# 20170814_DukeExperimentalHeadstageAmplif.net
KiCad netlist of a schematic drawn in EAGLE
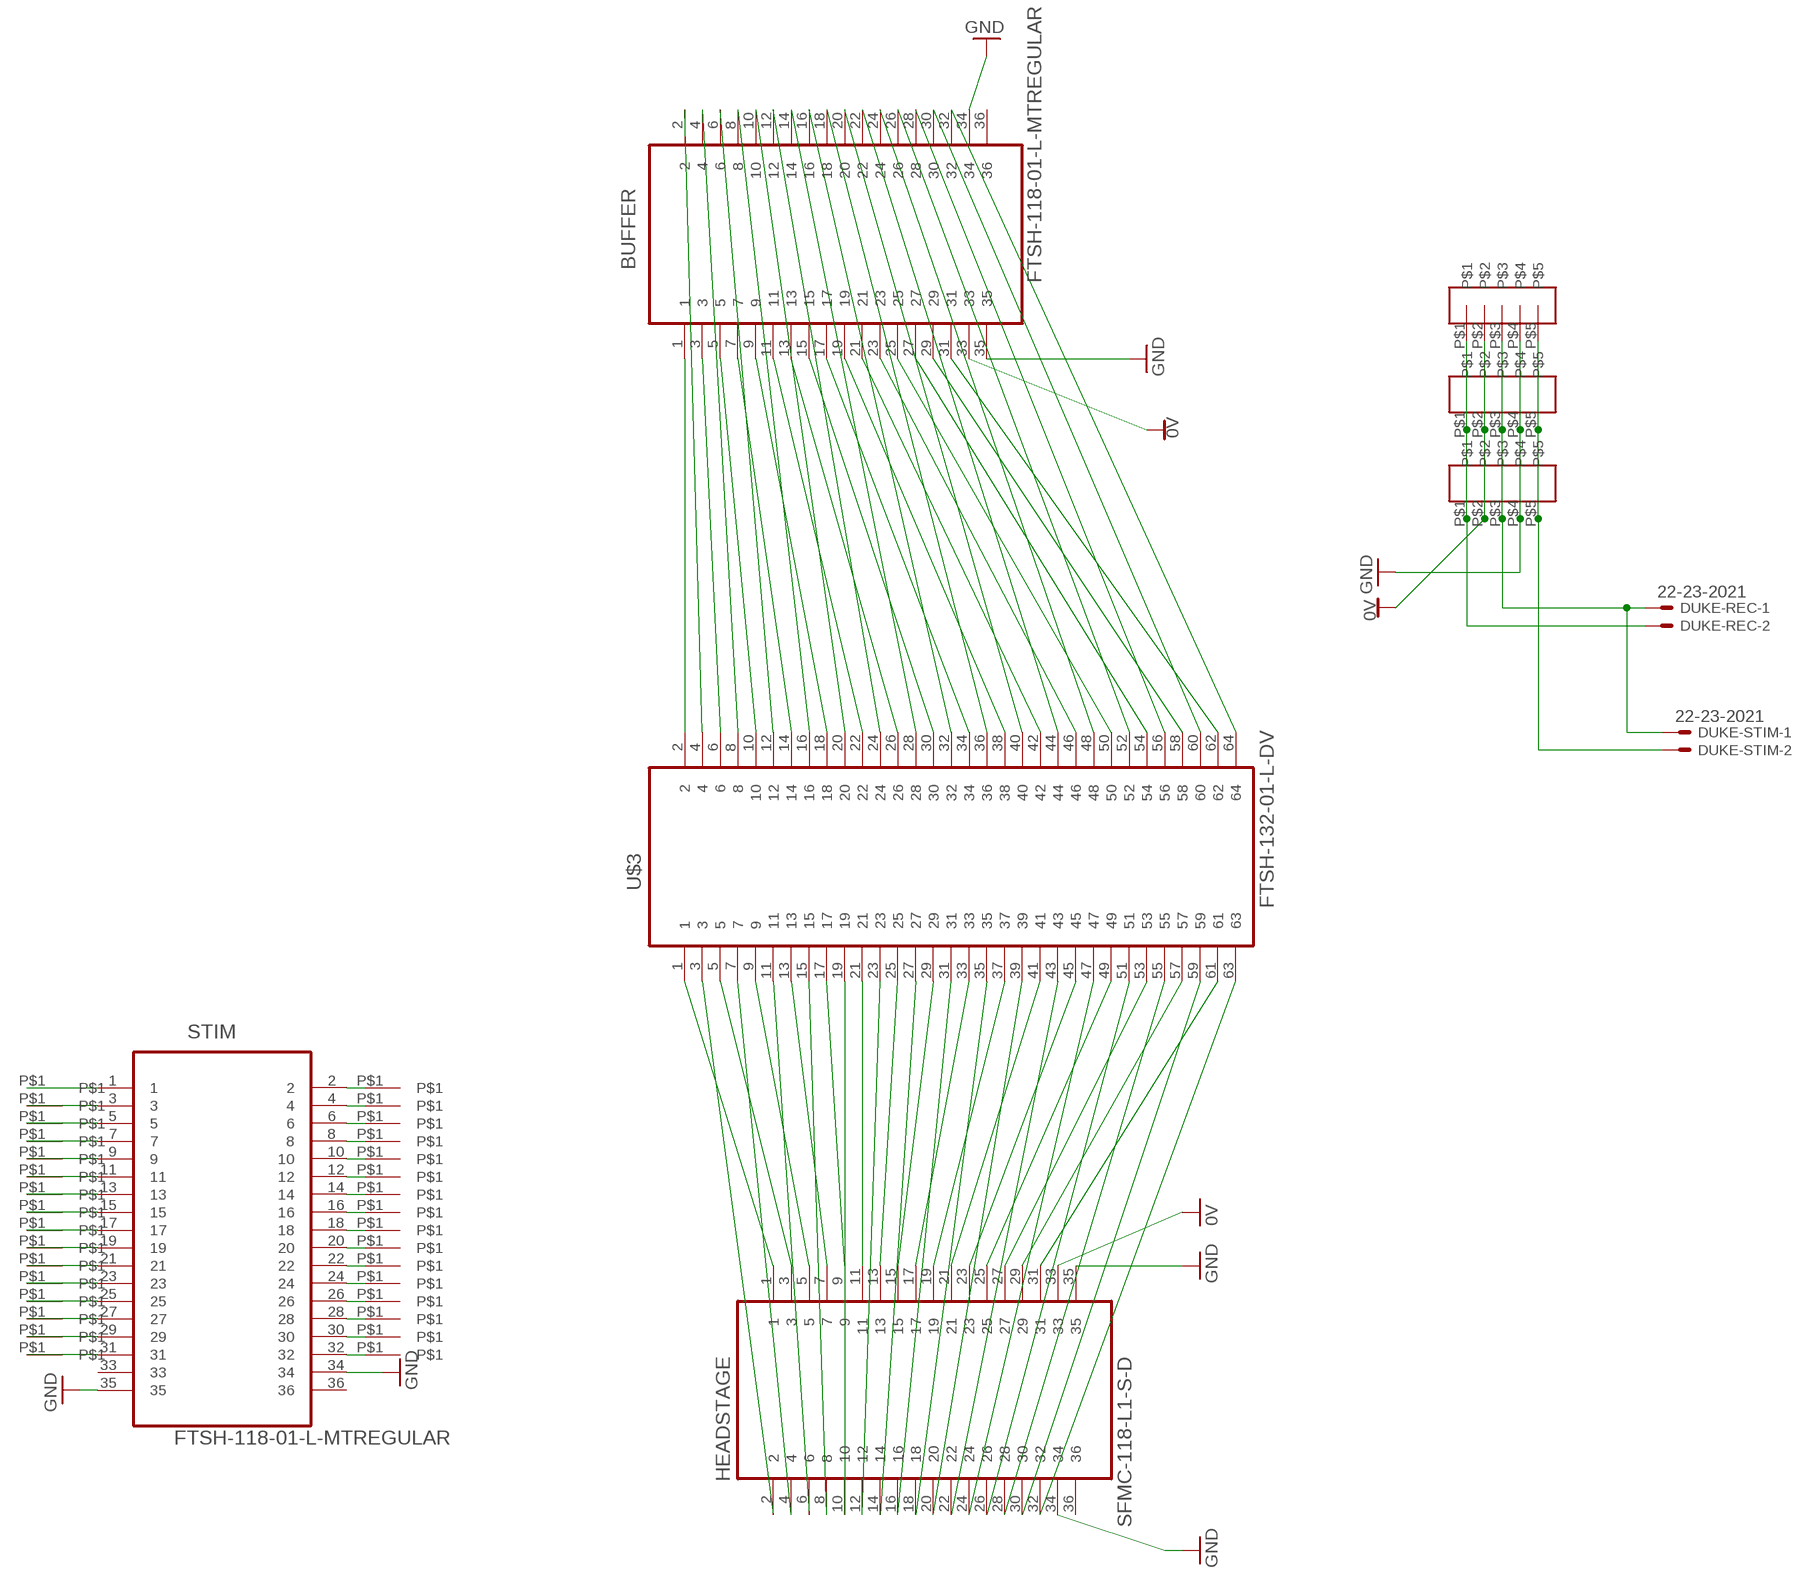
[diagram p0: schematic, sheet 1]

(export (version "E")
  (design (tool "Eeschema 10.0.6"))
  (components
    (comp (ref "BUFFER")
      (value "FTSH-118-01-L-MTREGULAR")
      (footprint "eagle-import:FTSH-118-01-L-MT")
      (libsource (lib "eagle-import") (part "FTSH-118-01-L-MTREGULAR"))
    )
    (comp (ref "DUKE-REC")
      (value "22-23-2021")
      (footprint "eagle-import:22-23-2021")
      (fields (field (name "MF") "MOLEX"))
      (libsource (lib "eagle-import") (part "22-23-2021"))
    )
    (comp (ref "DUKE-STIM")
      (value "22-23-2021")
      (footprint "eagle-import:22-23-2021")
      (fields (field (name "MF") "MOLEX"))
      (libsource (lib "eagle-import") (part "22-23-2021"))
    )
    (comp (ref "HEADSTAGE")
      (value "SFMC-118-L1-S-D")
      (footprint "eagle-import:SFMC-118-L1-S-D")
      (libsource (lib "eagle-import") (part "SFMC-118-L1-S-D"))
    )
    (comp (ref "STIM")
      (value "FTSH-118-01-L-MTREGULAR")
      (footprint "eagle-import:FTSH-118-01-L-MT")
      (libsource (lib "eagle-import") (part "FTSH-118-01-L-MTREGULAR"))
    )
    (comp (ref "U$1")
      (value "VIA")
      (footprint "eagle-import:VIA")
      (libsource (lib "eagle-import") (part "VIA"))
    )
    (comp (ref "U$2")
      (value "VIA")
      (footprint "eagle-import:VIA")
      (libsource (lib "eagle-import") (part "VIA"))
    )
    (comp (ref "U$3")
      (value "FTSH-132-01-L-DV")
      (footprint "eagle-import:FTSH-132-01-DV")
      (libsource (lib "eagle-import") (part "FTSH-132-01-L-DV"))
    )
    (comp (ref "U$4")
      (value "VIA")
      (footprint "eagle-import:VIA")
      (libsource (lib "eagle-import") (part "VIA"))
    )
    (comp (ref "U$5")
      (value "VIA")
      (footprint "eagle-import:VIA")
      (libsource (lib "eagle-import") (part "VIA"))
    )
    (comp (ref "U$6")
      (value "VIA")
      (footprint "eagle-import:VIA")
      (libsource (lib "eagle-import") (part "VIA"))
    )
    (comp (ref "U$7")
      (value "VIA")
      (footprint "eagle-import:VIA")
      (libsource (lib "eagle-import") (part "VIA"))
    )
    (comp (ref "U$8")
      (value "VIA")
      (footprint "eagle-import:VIA")
      (libsource (lib "eagle-import") (part "VIA"))
    )
    (comp (ref "U$9")
      (value "VIA")
      (footprint "eagle-import:VIA")
      (libsource (lib "eagle-import") (part "VIA"))
    )
    (comp (ref "U$10")
      (value "VIA")
      (footprint "eagle-import:VIA")
      (libsource (lib "eagle-import") (part "VIA"))
    )
    (comp (ref "U$11")
      (value "VIA")
      (footprint "eagle-import:VIA")
      (libsource (lib "eagle-import") (part "VIA"))
    )
    (comp (ref "U$12")
      (value "VIA")
      (footprint "eagle-import:VIA")
      (libsource (lib "eagle-import") (part "VIA"))
    )
    (comp (ref "U$13")
      (value "VIA")
      (footprint "eagle-import:VIA")
      (libsource (lib "eagle-import") (part "VIA"))
    )
    (comp (ref "U$14")
      (value "VIA")
      (footprint "eagle-import:VIA")
      (libsource (lib "eagle-import") (part "VIA"))
    )
    (comp (ref "U$15")
      (value "VIA")
      (footprint "eagle-import:VIA")
      (libsource (lib "eagle-import") (part "VIA"))
    )
    (comp (ref "U$16")
      (value "VIA")
      (footprint "eagle-import:VIA")
      (libsource (lib "eagle-import") (part "VIA"))
    )
    (comp (ref "U$17")
      (value "VIA")
      (footprint "eagle-import:VIA")
      (libsource (lib "eagle-import") (part "VIA"))
    )
    (comp (ref "U$18")
      (value "VIA")
      (footprint "eagle-import:VIA")
      (libsource (lib "eagle-import") (part "VIA"))
    )
    (comp (ref "U$19")
      (value "VIA")
      (footprint "eagle-import:VIA")
      (libsource (lib "eagle-import") (part "VIA"))
    )
    (comp (ref "U$20")
      (value "VIA")
      (footprint "eagle-import:VIA")
      (libsource (lib "eagle-import") (part "VIA"))
    )
    (comp (ref "U$21")
      (value "VIA")
      (footprint "eagle-import:VIA")
      (libsource (lib "eagle-import") (part "VIA"))
    )
    (comp (ref "U$22")
      (value "VIA")
      (footprint "eagle-import:VIA")
      (libsource (lib "eagle-import") (part "VIA"))
    )
    (comp (ref "U$23")
      (value "VIA")
      (footprint "eagle-import:VIA")
      (libsource (lib "eagle-import") (part "VIA"))
    )
    (comp (ref "U$24")
      (value "VIA")
      (footprint "eagle-import:VIA")
      (libsource (lib "eagle-import") (part "VIA"))
    )
    (comp (ref "U$25")
      (value "VIA")
      (footprint "eagle-import:VIA")
      (libsource (lib "eagle-import") (part "VIA"))
    )
    (comp (ref "U$26")
      (value "VIA")
      (footprint "eagle-import:VIA")
      (libsource (lib "eagle-import") (part "VIA"))
    )
    (comp (ref "U$27")
      (value "VIA")
      (footprint "eagle-import:VIA")
      (libsource (lib "eagle-import") (part "VIA"))
    )
    (comp (ref "U$28")
      (value "VIA")
      (footprint "eagle-import:VIA")
      (libsource (lib "eagle-import") (part "VIA"))
    )
    (comp (ref "U$29")
      (value "VIA")
      (footprint "eagle-import:VIA")
      (libsource (lib "eagle-import") (part "VIA"))
    )
    (comp (ref "U$30")
      (value "VIA")
      (footprint "eagle-import:VIA")
      (libsource (lib "eagle-import") (part "VIA"))
    )
    (comp (ref "U$31")
      (value "VIA")
      (footprint "eagle-import:VIA")
      (libsource (lib "eagle-import") (part "VIA"))
    )
    (comp (ref "U$32")
      (value "VIA")
      (footprint "eagle-import:VIA")
      (libsource (lib "eagle-import") (part "VIA"))
    )
    (comp (ref "U$33")
      (value "VIA")
      (footprint "eagle-import:VIA")
      (libsource (lib "eagle-import") (part "VIA"))
    )
    (comp (ref "U$34")
      (value "LPPB051NFFN-RC")
      (footprint "eagle-import:LPPB051NFFN-RC")
      (libsource (lib "eagle-import") (part "LPPB051NFFN-RC"))
    )
    (comp (ref "U$35")
      (value "LPPB051NFFN-RC")
      (footprint "eagle-import:LPPB051NFFN-RC")
      (libsource (lib "eagle-import") (part "LPPB051NFFN-RC"))
    )
    (comp (ref "U$36")
      (value "LPPB051NFFN-RC")
      (footprint "eagle-import:LPPB051NFFN-RC")
      (libsource (lib "eagle-import") (part "LPPB051NFFN-RC"))
    )
  )
  (nets
    (net (code "1") (name "0V") (class "Default")
      (node (ref "BUFFER") (pin "33") (pinfunction "33_33") (pintype "passive"))
      (node (ref "HEADSTAGE") (pin "33") (pinfunction "33_33") (pintype "passive"))
      (node (ref "U$34") (pin "P$2") (pinfunction "P$2_P$2") (pintype "bidirectional"))
      (node (ref "U$35") (pin "P$2") (pinfunction "P$2_P$2") (pintype "bidirectional"))
      (node (ref "U$36") (pin "P$2") (pinfunction "P$2_P$2") (pintype "bidirectional"))
    )
    (net (code "2") (name "GND") (class "Default")
      (node (ref "BUFFER") (pin "34") (pinfunction "34_34") (pintype "passive"))
      (node (ref "BUFFER") (pin "35") (pinfunction "35_35") (pintype "passive"))
      (node (ref "HEADSTAGE") (pin "34") (pinfunction "34_34") (pintype "passive"))
      (node (ref "HEADSTAGE") (pin "35") (pinfunction "35_35") (pintype "passive"))
      (node (ref "STIM") (pin "34") (pinfunction "34_34") (pintype "passive"))
      (node (ref "STIM") (pin "35") (pinfunction "35_35") (pintype "passive"))
      (node (ref "U$34") (pin "P$4") (pinfunction "P$4_P$4") (pintype "bidirectional"))
      (node (ref "U$35") (pin "P$4") (pinfunction "P$4_P$4") (pintype "bidirectional"))
      (node (ref "U$36") (pin "P$4") (pinfunction "P$4_P$4") (pintype "bidirectional"))
    )
    (net (code "3") (name "Net-(BUFFER-Pad1)") (class "Default")
      (node (ref "BUFFER") (pin "1") (pinfunction "1_1") (pintype "passive"))
      (node (ref "U$3") (pin "2") (pinfunction "2_2") (pintype "passive"))
    )
    (net (code "4") (name "Net-(BUFFER-Pad2)") (class "Default")
      (node (ref "BUFFER") (pin "2") (pinfunction "2_2") (pintype "passive"))
      (node (ref "U$3") (pin "4") (pinfunction "4_4") (pintype "passive"))
    )
    (net (code "5") (name "Net-(BUFFER-Pad3)") (class "Default")
      (node (ref "BUFFER") (pin "3") (pinfunction "3_3") (pintype "passive"))
      (node (ref "U$3") (pin "6") (pinfunction "6_6") (pintype "passive"))
    )
    (net (code "6") (name "Net-(BUFFER-Pad4)") (class "Default")
      (node (ref "BUFFER") (pin "4") (pinfunction "4_4") (pintype "passive"))
      (node (ref "U$3") (pin "8") (pinfunction "8_8") (pintype "passive"))
    )
    (net (code "7") (name "Net-(BUFFER-Pad5)") (class "Default")
      (node (ref "BUFFER") (pin "5") (pinfunction "5_5") (pintype "passive"))
      (node (ref "U$3") (pin "10") (pinfunction "10_10") (pintype "passive"))
    )
    (net (code "8") (name "Net-(BUFFER-Pad6)") (class "Default")
      (node (ref "BUFFER") (pin "6") (pinfunction "6_6") (pintype "passive"))
      (node (ref "U$3") (pin "12") (pinfunction "12_12") (pintype "passive"))
    )
    (net (code "9") (name "Net-(BUFFER-Pad7)") (class "Default")
      (node (ref "BUFFER") (pin "7") (pinfunction "7_7") (pintype "passive"))
      (node (ref "U$3") (pin "14") (pinfunction "14_14") (pintype "passive"))
    )
    (net (code "10") (name "Net-(BUFFER-Pad8)") (class "Default")
      (node (ref "BUFFER") (pin "8") (pinfunction "8_8") (pintype "passive"))
      (node (ref "U$3") (pin "16") (pinfunction "16_16") (pintype "passive"))
    )
    (net (code "11") (name "Net-(BUFFER-Pad9)") (class "Default")
      (node (ref "BUFFER") (pin "9") (pinfunction "9_9") (pintype "passive"))
      (node (ref "U$3") (pin "18") (pinfunction "18_18") (pintype "passive"))
    )
    (net (code "12") (name "Net-(BUFFER-Pad10)") (class "Default")
      (node (ref "BUFFER") (pin "10") (pinfunction "10_10") (pintype "passive"))
      (node (ref "U$3") (pin "20") (pinfunction "20_20") (pintype "passive"))
    )
    (net (code "13") (name "Net-(BUFFER-Pad11)") (class "Default")
      (node (ref "BUFFER") (pin "11") (pinfunction "11_11") (pintype "passive"))
      (node (ref "U$3") (pin "22") (pinfunction "22_22") (pintype "passive"))
    )
    (net (code "14") (name "Net-(BUFFER-Pad12)") (class "Default")
      (node (ref "BUFFER") (pin "12") (pinfunction "12_12") (pintype "passive"))
      (node (ref "U$3") (pin "24") (pinfunction "24_24") (pintype "passive"))
    )
    (net (code "15") (name "Net-(BUFFER-Pad13)") (class "Default")
      (node (ref "BUFFER") (pin "13") (pinfunction "13_13") (pintype "passive"))
      (node (ref "U$3") (pin "26") (pinfunction "26_26") (pintype "passive"))
    )
    (net (code "16") (name "Net-(BUFFER-Pad14)") (class "Default")
      (node (ref "BUFFER") (pin "14") (pinfunction "14_14") (pintype "passive"))
      (node (ref "U$3") (pin "28") (pinfunction "28_28") (pintype "passive"))
    )
    (net (code "17") (name "Net-(BUFFER-Pad15)") (class "Default")
      (node (ref "BUFFER") (pin "15") (pinfunction "15_15") (pintype "passive"))
      (node (ref "U$3") (pin "30") (pinfunction "30_30") (pintype "passive"))
    )
    (net (code "18") (name "Net-(BUFFER-Pad16)") (class "Default")
      (node (ref "BUFFER") (pin "16") (pinfunction "16_16") (pintype "passive"))
      (node (ref "U$3") (pin "32") (pinfunction "32_32") (pintype "passive"))
    )
    (net (code "19") (name "Net-(BUFFER-Pad17)") (class "Default")
      (node (ref "BUFFER") (pin "17") (pinfunction "17_17") (pintype "passive"))
      (node (ref "U$3") (pin "34") (pinfunction "34_34") (pintype "passive"))
    )
    (net (code "20") (name "Net-(BUFFER-Pad18)") (class "Default")
      (node (ref "BUFFER") (pin "18") (pinfunction "18_18") (pintype "passive"))
      (node (ref "U$3") (pin "36") (pinfunction "36_36") (pintype "passive"))
    )
    (net (code "21") (name "Net-(BUFFER-Pad19)") (class "Default")
      (node (ref "BUFFER") (pin "19") (pinfunction "19_19") (pintype "passive"))
      (node (ref "U$3") (pin "38") (pinfunction "38_38") (pintype "bidirectional"))
    )
    (net (code "22") (name "Net-(BUFFER-Pad20)") (class "Default")
      (node (ref "BUFFER") (pin "20") (pinfunction "20_20") (pintype "passive"))
      (node (ref "U$3") (pin "40") (pinfunction "40_40") (pintype "bidirectional"))
    )
    (net (code "23") (name "Net-(BUFFER-Pad21)") (class "Default")
      (node (ref "BUFFER") (pin "21") (pinfunction "21_21") (pintype "passive"))
      (node (ref "U$3") (pin "42") (pinfunction "42_42") (pintype "bidirectional"))
    )
    (net (code "24") (name "Net-(BUFFER-Pad22)") (class "Default")
      (node (ref "BUFFER") (pin "22") (pinfunction "22_22") (pintype "passive"))
      (node (ref "U$3") (pin "44") (pinfunction "44_44") (pintype "bidirectional"))
    )
    (net (code "25") (name "Net-(BUFFER-Pad23)") (class "Default")
      (node (ref "BUFFER") (pin "23") (pinfunction "23_23") (pintype "passive"))
      (node (ref "U$3") (pin "46") (pinfunction "46_46") (pintype "bidirectional"))
    )
    (net (code "26") (name "Net-(BUFFER-Pad24)") (class "Default")
      (node (ref "BUFFER") (pin "24") (pinfunction "24_24") (pintype "passive"))
      (node (ref "U$3") (pin "48") (pinfunction "48_48") (pintype "bidirectional"))
    )
    (net (code "27") (name "Net-(BUFFER-Pad25)") (class "Default")
      (node (ref "BUFFER") (pin "25") (pinfunction "25_25") (pintype "passive"))
      (node (ref "U$3") (pin "50") (pinfunction "50_50") (pintype "bidirectional"))
    )
    (net (code "28") (name "Net-(BUFFER-Pad26)") (class "Default")
      (node (ref "BUFFER") (pin "26") (pinfunction "26_26") (pintype "passive"))
      (node (ref "U$3") (pin "52") (pinfunction "52_52") (pintype "bidirectional"))
    )
    (net (code "29") (name "Net-(BUFFER-Pad27)") (class "Default")
      (node (ref "BUFFER") (pin "27") (pinfunction "27_27") (pintype "passive"))
      (node (ref "U$3") (pin "54") (pinfunction "54_54") (pintype "bidirectional"))
    )
    (net (code "30") (name "Net-(BUFFER-Pad28)") (class "Default")
      (node (ref "BUFFER") (pin "28") (pinfunction "28_28") (pintype "passive"))
      (node (ref "U$3") (pin "56") (pinfunction "56_56") (pintype "bidirectional"))
    )
    (net (code "31") (name "Net-(BUFFER-Pad29)") (class "Default")
      (node (ref "BUFFER") (pin "29") (pinfunction "29_29") (pintype "passive"))
      (node (ref "U$3") (pin "58") (pinfunction "58_58") (pintype "bidirectional"))
    )
    (net (code "32") (name "Net-(BUFFER-Pad30)") (class "Default")
      (node (ref "BUFFER") (pin "30") (pinfunction "30_30") (pintype "passive"))
      (node (ref "U$3") (pin "60") (pinfunction "60_60") (pintype "bidirectional"))
    )
    (net (code "33") (name "Net-(BUFFER-Pad31)") (class "Default")
      (node (ref "BUFFER") (pin "31") (pinfunction "31_31") (pintype "passive"))
      (node (ref "U$3") (pin "62") (pinfunction "62_62") (pintype "bidirectional"))
    )
    (net (code "34") (name "Net-(BUFFER-Pad32)") (class "Default")
      (node (ref "BUFFER") (pin "32") (pinfunction "32_32") (pintype "passive"))
      (node (ref "U$3") (pin "64") (pinfunction "64_64") (pintype "bidirectional"))
    )
    (net (code "35") (name "Net-(DUKE-RECA-S)") (class "Default")
      (node (ref "DUKE-REC") (pin "1") (pinfunction "S_1") (pintype "passive"))
      (node (ref "DUKE-STIM") (pin "1") (pinfunction "S_1") (pintype "passive"))
      (node (ref "U$34") (pin "P$3") (pinfunction "P$3_P$3") (pintype "bidirectional"))
      (node (ref "U$35") (pin "P$3") (pinfunction "P$3_P$3") (pintype "bidirectional"))
      (node (ref "U$36") (pin "P$3") (pinfunction "P$3_P$3") (pintype "bidirectional"))
    )
    (net (code "36") (name "Net-(DUKE-RECB-S)") (class "Default")
      (node (ref "DUKE-REC") (pin "2") (pinfunction "S_2") (pintype "passive"))
      (node (ref "U$34") (pin "P$1") (pinfunction "P$1_P$1") (pintype "bidirectional"))
      (node (ref "U$35") (pin "P$1") (pinfunction "P$1_P$1") (pintype "bidirectional"))
      (node (ref "U$36") (pin "P$1") (pinfunction "P$1_P$1") (pintype "bidirectional"))
    )
    (net (code "37") (name "Net-(DUKE-STIMB-S)") (class "Default")
      (node (ref "DUKE-STIM") (pin "2") (pinfunction "S_2") (pintype "passive"))
      (node (ref "U$34") (pin "P$5") (pinfunction "P$5_P$5") (pintype "bidirectional"))
      (node (ref "U$35") (pin "P$5") (pinfunction "P$5_P$5") (pintype "bidirectional"))
      (node (ref "U$36") (pin "P$5") (pinfunction "P$5_P$5") (pintype "bidirectional"))
    )
    (net (code "38") (name "Net-(HEADSTAGE-Pad1)") (class "Default")
      (node (ref "HEADSTAGE") (pin "1") (pinfunction "1_1") (pintype "passive"))
      (node (ref "U$3") (pin "1") (pinfunction "1_1") (pintype "passive"))
    )
    (net (code "39") (name "Net-(HEADSTAGE-Pad2)") (class "Default")
      (node (ref "HEADSTAGE") (pin "2") (pinfunction "2_2") (pintype "passive"))
      (node (ref "U$3") (pin "3") (pinfunction "3_3") (pintype "passive"))
    )
    (net (code "40") (name "Net-(HEADSTAGE-Pad3)") (class "Default")
      (node (ref "HEADSTAGE") (pin "3") (pinfunction "3_3") (pintype "passive"))
      (node (ref "U$3") (pin "5") (pinfunction "5_5") (pintype "passive"))
    )
    (net (code "41") (name "Net-(HEADSTAGE-Pad4)") (class "Default")
      (node (ref "HEADSTAGE") (pin "4") (pinfunction "4_4") (pintype "passive"))
      (node (ref "U$3") (pin "7") (pinfunction "7_7") (pintype "passive"))
    )
    (net (code "42") (name "Net-(HEADSTAGE-Pad5)") (class "Default")
      (node (ref "HEADSTAGE") (pin "5") (pinfunction "5_5") (pintype "passive"))
      (node (ref "U$3") (pin "9") (pinfunction "9_9") (pintype "passive"))
    )
    (net (code "43") (name "Net-(HEADSTAGE-Pad6)") (class "Default")
      (node (ref "HEADSTAGE") (pin "6") (pinfunction "6_6") (pintype "passive"))
      (node (ref "U$3") (pin "11") (pinfunction "11_11") (pintype "passive"))
    )
    (net (code "44") (name "Net-(HEADSTAGE-Pad7)") (class "Default")
      (node (ref "HEADSTAGE") (pin "7") (pinfunction "7_7") (pintype "passive"))
      (node (ref "U$3") (pin "13") (pinfunction "13_13") (pintype "passive"))
    )
    (net (code "45") (name "Net-(HEADSTAGE-Pad8)") (class "Default")
      (node (ref "HEADSTAGE") (pin "8") (pinfunction "8_8") (pintype "passive"))
      (node (ref "U$3") (pin "15") (pinfunction "15_15") (pintype "passive"))
    )
    (net (code "46") (name "Net-(HEADSTAGE-Pad9)") (class "Default")
      (node (ref "HEADSTAGE") (pin "9") (pinfunction "9_9") (pintype "passive"))
      (node (ref "U$3") (pin "17") (pinfunction "17_17") (pintype "passive"))
    )
    (net (code "47") (name "Net-(HEADSTAGE-Pad10)") (class "Default")
      (node (ref "HEADSTAGE") (pin "10") (pinfunction "10_10") (pintype "passive"))
      (node (ref "U$3") (pin "19") (pinfunction "19_19") (pintype "passive"))
    )
    (net (code "48") (name "Net-(HEADSTAGE-Pad11)") (class "Default")
      (node (ref "HEADSTAGE") (pin "11") (pinfunction "11_11") (pintype "passive"))
      (node (ref "U$3") (pin "21") (pinfunction "21_21") (pintype "passive"))
    )
    (net (code "49") (name "Net-(HEADSTAGE-Pad12)") (class "Default")
      (node (ref "HEADSTAGE") (pin "12") (pinfunction "12_12") (pintype "passive"))
      (node (ref "U$3") (pin "23") (pinfunction "23_23") (pintype "passive"))
    )
    (net (code "50") (name "Net-(HEADSTAGE-Pad13)") (class "Default")
      (node (ref "HEADSTAGE") (pin "13") (pinfunction "13_13") (pintype "passive"))
      (node (ref "U$3") (pin "25") (pinfunction "25_25") (pintype "passive"))
    )
    (net (code "51") (name "Net-(HEADSTAGE-Pad14)") (class "Default")
      (node (ref "HEADSTAGE") (pin "14") (pinfunction "14_14") (pintype "passive"))
      (node (ref "U$3") (pin "27") (pinfunction "27_27") (pintype "passive"))
    )
    (net (code "52") (name "Net-(HEADSTAGE-Pad15)") (class "Default")
      (node (ref "HEADSTAGE") (pin "15") (pinfunction "15_15") (pintype "passive"))
      (node (ref "U$3") (pin "29") (pinfunction "29_29") (pintype "passive"))
    )
    (net (code "53") (name "Net-(HEADSTAGE-Pad16)") (class "Default")
      (node (ref "HEADSTAGE") (pin "16") (pinfunction "16_16") (pintype "passive"))
      (node (ref "U$3") (pin "31") (pinfunction "31_31") (pintype "passive"))
    )
    (net (code "54") (name "Net-(HEADSTAGE-Pad17)") (class "Default")
      (node (ref "HEADSTAGE") (pin "17") (pinfunction "17_17") (pintype "passive"))
      (node (ref "U$3") (pin "33") (pinfunction "33_33") (pintype "passive"))
    )
    (net (code "55") (name "Net-(HEADSTAGE-Pad18)") (class "Default")
      (node (ref "HEADSTAGE") (pin "18") (pinfunction "18_18") (pintype "passive"))
      (node (ref "U$3") (pin "35") (pinfunction "35_35") (pintype "passive"))
    )
    (net (code "56") (name "Net-(HEADSTAGE-Pad19)") (class "Default")
      (node (ref "HEADSTAGE") (pin "19") (pinfunction "19_19") (pintype "passive"))
      (node (ref "U$3") (pin "37") (pinfunction "37_37") (pintype "bidirectional"))
    )
    (net (code "57") (name "Net-(HEADSTAGE-Pad20)") (class "Default")
      (node (ref "HEADSTAGE") (pin "20") (pinfunction "20_20") (pintype "passive"))
      (node (ref "U$3") (pin "39") (pinfunction "39_39") (pintype "bidirectional"))
    )
    (net (code "58") (name "Net-(HEADSTAGE-Pad21)") (class "Default")
      (node (ref "HEADSTAGE") (pin "21") (pinfunction "21_21") (pintype "passive"))
      (node (ref "U$3") (pin "41") (pinfunction "41_41") (pintype "bidirectional"))
    )
    (net (code "59") (name "Net-(HEADSTAGE-Pad22)") (class "Default")
      (node (ref "HEADSTAGE") (pin "22") (pinfunction "22_22") (pintype "passive"))
      (node (ref "U$3") (pin "43") (pinfunction "43_43") (pintype "bidirectional"))
    )
    (net (code "60") (name "Net-(HEADSTAGE-Pad23)") (class "Default")
      (node (ref "HEADSTAGE") (pin "23") (pinfunction "23_23") (pintype "passive"))
      (node (ref "U$3") (pin "45") (pinfunction "45_45") (pintype "bidirectional"))
    )
    (net (code "61") (name "Net-(HEADSTAGE-Pad24)") (class "Default")
      (node (ref "HEADSTAGE") (pin "24") (pinfunction "24_24") (pintype "passive"))
      (node (ref "U$3") (pin "47") (pinfunction "47_47") (pintype "bidirectional"))
    )
    (net (code "62") (name "Net-(HEADSTAGE-Pad25)") (class "Default")
      (node (ref "HEADSTAGE") (pin "25") (pinfunction "25_25") (pintype "passive"))
      (node (ref "U$3") (pin "49") (pinfunction "49_49") (pintype "bidirectional"))
    )
    (net (code "63") (name "Net-(HEADSTAGE-Pad26)") (class "Default")
      (node (ref "HEADSTAGE") (pin "26") (pinfunction "26_26") (pintype "passive"))
      (node (ref "U$3") (pin "51") (pinfunction "51_51") (pintype "bidirectional"))
    )
    (net (code "64") (name "Net-(HEADSTAGE-Pad27)") (class "Default")
      (node (ref "HEADSTAGE") (pin "27") (pinfunction "27_27") (pintype "passive"))
      (node (ref "U$3") (pin "53") (pinfunction "53_53") (pintype "bidirectional"))
    )
    (net (code "65") (name "Net-(HEADSTAGE-Pad28)") (class "Default")
      (node (ref "HEADSTAGE") (pin "28") (pinfunction "28_28") (pintype "passive"))
      (node (ref "U$3") (pin "55") (pinfunction "55_55") (pintype "bidirectional"))
    )
    (net (code "66") (name "Net-(HEADSTAGE-Pad29)") (class "Default")
      (node (ref "HEADSTAGE") (pin "29") (pinfunction "29_29") (pintype "passive"))
      (node (ref "U$3") (pin "57") (pinfunction "57_57") (pintype "bidirectional"))
    )
    (net (code "67") (name "Net-(HEADSTAGE-Pad30)") (class "Default")
      (node (ref "HEADSTAGE") (pin "30") (pinfunction "30_30") (pintype "passive"))
      (node (ref "U$3") (pin "59") (pinfunction "59_59") (pintype "bidirectional"))
    )
    (net (code "68") (name "Net-(HEADSTAGE-Pad31)") (class "Default")
      (node (ref "HEADSTAGE") (pin "31") (pinfunction "31_31") (pintype "passive"))
      (node (ref "U$3") (pin "61") (pinfunction "61_61") (pintype "bidirectional"))
    )
    (net (code "69") (name "Net-(HEADSTAGE-Pad32)") (class "Default")
      (node (ref "HEADSTAGE") (pin "32") (pinfunction "32_32") (pintype "passive"))
      (node (ref "U$3") (pin "63") (pinfunction "63_63") (pintype "bidirectional"))
    )
    (net (code "70") (name "Net-(STIM-Pad1)") (class "Default")
      (node (ref "STIM") (pin "1") (pinfunction "1_1") (pintype "passive"))
      (node (ref "U$33") (pin "P$1") (pinfunction "P$1_P$1") (pintype "bidirectional"))
    )
    (net (code "71") (name "Net-(STIM-Pad2)") (class "Default")
      (node (ref "STIM") (pin "2") (pinfunction "2_2") (pintype "passive"))
      (node (ref "U$1") (pin "P$1") (pinfunction "P$1_P$1") (pintype "bidirectional"))
    )
    (net (code "72") (name "Net-(STIM-Pad3)") (class "Default")
      (node (ref "STIM") (pin "3") (pinfunction "3_3") (pintype "passive"))
      (node (ref "U$32") (pin "P$1") (pinfunction "P$1_P$1") (pintype "bidirectional"))
    )
    (net (code "73") (name "Net-(STIM-Pad4)") (class "Default")
      (node (ref "STIM") (pin "4") (pinfunction "4_4") (pintype "passive"))
      (node (ref "U$2") (pin "P$1") (pinfunction "P$1_P$1") (pintype "bidirectional"))
    )
    (net (code "74") (name "Net-(STIM-Pad5)") (class "Default")
      (node (ref "STIM") (pin "5") (pinfunction "5_5") (pintype "passive"))
      (node (ref "U$31") (pin "P$1") (pinfunction "P$1_P$1") (pintype "bidirectional"))
    )
    (net (code "75") (name "Net-(STIM-Pad6)") (class "Default")
      (node (ref "STIM") (pin "6") (pinfunction "6_6") (pintype "passive"))
      (node (ref "U$4") (pin "P$1") (pinfunction "P$1_P$1") (pintype "bidirectional"))
    )
    (net (code "76") (name "Net-(STIM-Pad7)") (class "Default")
      (node (ref "STIM") (pin "7") (pinfunction "7_7") (pintype "passive"))
      (node (ref "U$30") (pin "P$1") (pinfunction "P$1_P$1") (pintype "bidirectional"))
    )
    (net (code "77") (name "Net-(STIM-Pad8)") (class "Default")
      (node (ref "STIM") (pin "8") (pinfunction "8_8") (pintype "passive"))
      (node (ref "U$5") (pin "P$1") (pinfunction "P$1_P$1") (pintype "bidirectional"))
    )
    (net (code "78") (name "Net-(STIM-Pad9)") (class "Default")
      (node (ref "STIM") (pin "9") (pinfunction "9_9") (pintype "passive"))
      (node (ref "U$29") (pin "P$1") (pinfunction "P$1_P$1") (pintype "bidirectional"))
    )
    (net (code "79") (name "Net-(STIM-Pad10)") (class "Default")
      (node (ref "STIM") (pin "10") (pinfunction "10_10") (pintype "passive"))
      (node (ref "U$6") (pin "P$1") (pinfunction "P$1_P$1") (pintype "bidirectional"))
    )
    (net (code "80") (name "Net-(STIM-Pad11)") (class "Default")
      (node (ref "STIM") (pin "11") (pinfunction "11_11") (pintype "passive"))
      (node (ref "U$28") (pin "P$1") (pinfunction "P$1_P$1") (pintype "bidirectional"))
    )
    (net (code "81") (name "Net-(STIM-Pad12)") (class "Default")
      (node (ref "STIM") (pin "12") (pinfunction "12_12") (pintype "passive"))
      (node (ref "U$7") (pin "P$1") (pinfunction "P$1_P$1") (pintype "bidirectional"))
    )
    (net (code "82") (name "Net-(STIM-Pad13)") (class "Default")
      (node (ref "STIM") (pin "13") (pinfunction "13_13") (pintype "passive"))
      (node (ref "U$27") (pin "P$1") (pinfunction "P$1_P$1") (pintype "bidirectional"))
    )
    (net (code "83") (name "Net-(STIM-Pad14)") (class "Default")
      (node (ref "STIM") (pin "14") (pinfunction "14_14") (pintype "passive"))
      (node (ref "U$8") (pin "P$1") (pinfunction "P$1_P$1") (pintype "bidirectional"))
    )
    (net (code "84") (name "Net-(STIM-Pad15)") (class "Default")
      (node (ref "STIM") (pin "15") (pinfunction "15_15") (pintype "passive"))
      (node (ref "U$26") (pin "P$1") (pinfunction "P$1_P$1") (pintype "bidirectional"))
    )
    (net (code "85") (name "Net-(STIM-Pad16)") (class "Default")
      (node (ref "STIM") (pin "16") (pinfunction "16_16") (pintype "passive"))
      (node (ref "U$9") (pin "P$1") (pinfunction "P$1_P$1") (pintype "bidirectional"))
    )
    (net (code "86") (name "Net-(STIM-Pad17)") (class "Default")
      (node (ref "STIM") (pin "17") (pinfunction "17_17") (pintype "passive"))
      (node (ref "U$25") (pin "P$1") (pinfunction "P$1_P$1") (pintype "bidirectional"))
    )
    (net (code "87") (name "Net-(STIM-Pad18)") (class "Default")
      (node (ref "STIM") (pin "18") (pinfunction "18_18") (pintype "passive"))
      (node (ref "U$10") (pin "P$1") (pinfunction "P$1_P$1") (pintype "bidirectional"))
    )
    (net (code "88") (name "Net-(STIM-Pad19)") (class "Default")
      (node (ref "STIM") (pin "19") (pinfunction "19_19") (pintype "passive"))
      (node (ref "U$24") (pin "P$1") (pinfunction "P$1_P$1") (pintype "bidirectional"))
    )
    (net (code "89") (name "Net-(STIM-Pad20)") (class "Default")
      (node (ref "STIM") (pin "20") (pinfunction "20_20") (pintype "passive"))
      (node (ref "U$11") (pin "P$1") (pinfunction "P$1_P$1") (pintype "bidirectional"))
    )
    (net (code "90") (name "Net-(STIM-Pad21)") (class "Default")
      (node (ref "STIM") (pin "21") (pinfunction "21_21") (pintype "passive"))
      (node (ref "U$23") (pin "P$1") (pinfunction "P$1_P$1") (pintype "bidirectional"))
    )
    (net (code "91") (name "Net-(STIM-Pad22)") (class "Default")
      (node (ref "STIM") (pin "22") (pinfunction "22_22") (pintype "passive"))
      (node (ref "U$12") (pin "P$1") (pinfunction "P$1_P$1") (pintype "bidirectional"))
    )
    (net (code "92") (name "Net-(STIM-Pad23)") (class "Default")
      (node (ref "STIM") (pin "23") (pinfunction "23_23") (pintype "passive"))
      (node (ref "U$22") (pin "P$1") (pinfunction "P$1_P$1") (pintype "bidirectional"))
    )
    (net (code "93") (name "Net-(STIM-Pad24)") (class "Default")
      (node (ref "STIM") (pin "24") (pinfunction "24_24") (pintype "passive"))
      (node (ref "U$13") (pin "P$1") (pinfunction "P$1_P$1") (pintype "bidirectional"))
    )
    (net (code "94") (name "Net-(STIM-Pad25)") (class "Default")
      (node (ref "STIM") (pin "25") (pinfunction "25_25") (pintype "passive"))
      (node (ref "U$21") (pin "P$1") (pinfunction "P$1_P$1") (pintype "bidirectional"))
    )
    (net (code "95") (name "Net-(STIM-Pad26)") (class "Default")
      (node (ref "STIM") (pin "26") (pinfunction "26_26") (pintype "passive"))
      (node (ref "U$14") (pin "P$1") (pinfunction "P$1_P$1") (pintype "bidirectional"))
    )
    (net (code "96") (name "Net-(STIM-Pad27)") (class "Default")
      (node (ref "STIM") (pin "27") (pinfunction "27_27") (pintype "passive"))
      (node (ref "U$20") (pin "P$1") (pinfunction "P$1_P$1") (pintype "bidirectional"))
    )
    (net (code "97") (name "Net-(STIM-Pad28)") (class "Default")
      (node (ref "STIM") (pin "28") (pinfunction "28_28") (pintype "passive"))
      (node (ref "U$15") (pin "P$1") (pinfunction "P$1_P$1") (pintype "bidirectional"))
    )
    (net (code "98") (name "Net-(STIM-Pad29)") (class "Default")
      (node (ref "STIM") (pin "29") (pinfunction "29_29") (pintype "passive"))
      (node (ref "U$19") (pin "P$1") (pinfunction "P$1_P$1") (pintype "bidirectional"))
    )
    (net (code "99") (name "Net-(STIM-Pad30)") (class "Default")
      (node (ref "STIM") (pin "30") (pinfunction "30_30") (pintype "passive"))
      (node (ref "U$16") (pin "P$1") (pinfunction "P$1_P$1") (pintype "bidirectional"))
    )
    (net (code "100") (name "Net-(STIM-Pad31)") (class "Default")
      (node (ref "STIM") (pin "31") (pinfunction "31_31") (pintype "passive"))
      (node (ref "U$18") (pin "P$1") (pinfunction "P$1_P$1") (pintype "bidirectional"))
    )
    (net (code "101") (name "Net-(STIM-Pad32)") (class "Default")
      (node (ref "STIM") (pin "32") (pinfunction "32_32") (pintype "passive"))
      (node (ref "U$17") (pin "P$1") (pinfunction "P$1_P$1") (pintype "bidirectional"))
    )
    (net (code "102") (name "unconnected-(BUFFER-Pad36)") (class "Default")
      (node (ref "BUFFER") (pin "36") (pinfunction "36_36") (pintype "passive"))
    )
    (net (code "103") (name "unconnected-(HEADSTAGE-Pad36)") (class "Default")
      (node (ref "HEADSTAGE") (pin "36") (pinfunction "36_36") (pintype "passive"))
    )
    (net (code "104") (name "unconnected-(STIM-Pad33)") (class "Default")
      (node (ref "STIM") (pin "33") (pinfunction "33_33") (pintype "passive"))
    )
    (net (code "105") (name "unconnected-(STIM-Pad36)") (class "Default")
      (node (ref "STIM") (pin "36") (pinfunction "36_36") (pintype "passive"))
    )
  )
)
